# NRF24L01.net
KiCad netlist of a schematic drawn in EAGLE
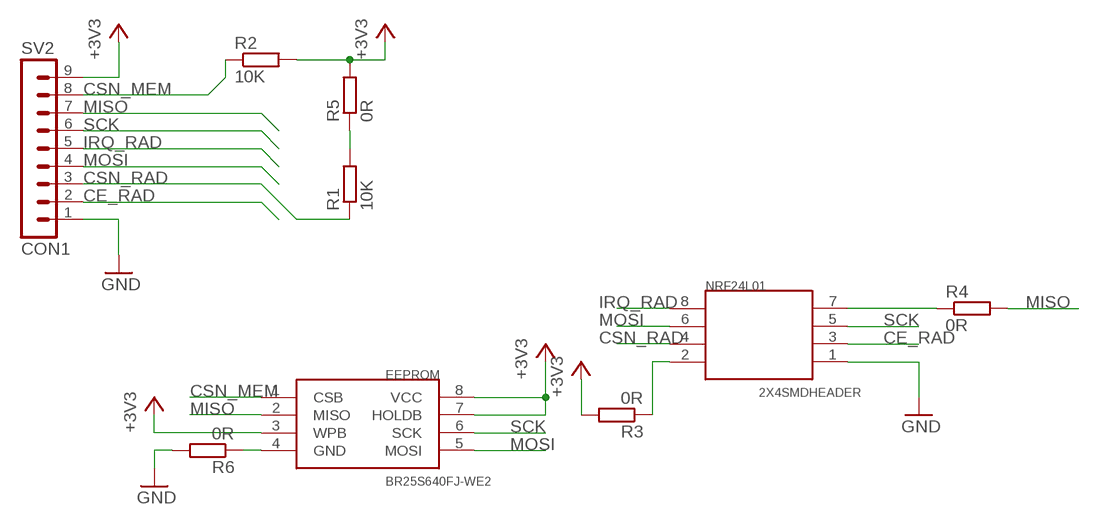
[diagram p0: schematic, sheet 1]

(export (version "E")
  (design (tool "Eeschema 10.0.6"))
  (components
    (comp (ref "EEPROM")
      (value "BR25S640FJ-WE2")
      (footprint "eagle-import:SO8")
      (libsource (lib "eagle-import") (part "BR25S640FJ-WE2"))
    )
    (comp (ref "NRF24L01")
      (value "2X4SMDHEADER")
      (footprint "eagle-import:TSM-110-XX-XXX-DV")
      (libsource (lib "eagle-import") (part "2X4SMDHEADER"))
    )
    (comp (ref "R1")
      (value "10K")
      (footprint "eagle-import:R1206")
      (libsource (lib "eagle-import") (part "R-EU_R1206"))
    )
    (comp (ref "R2")
      (value "10K")
      (footprint "eagle-import:R1206")
      (libsource (lib "eagle-import") (part "R-EU_R1206"))
    )
    (comp (ref "R3")
      (value "0R")
      (footprint "eagle-import:R1206")
      (libsource (lib "eagle-import") (part "R-EU_R1206"))
    )
    (comp (ref "R4")
      (value "0R")
      (footprint "eagle-import:R1206")
      (libsource (lib "eagle-import") (part "R-EU_R1206"))
    )
    (comp (ref "R5")
      (value "0R")
      (footprint "eagle-import:R1206")
      (libsource (lib "eagle-import") (part "R-EU_R1206"))
    )
    (comp (ref "R6")
      (value "0R")
      (footprint "eagle-import:R1206")
      (libsource (lib "eagle-import") (part "R-EU_R1206"))
    )
    (comp (ref "SV2")
      (value "CON1")
      (footprint "eagle-import:MA09-1W")
      (libsource (lib "eagle-import") (part "MA09-1W"))
    )
  )
  (nets
    (net (code "1") (name "+3V3") (class "Default")
      (node (ref "EEPROM") (pin "3") (pinfunction "WPB_3") (pintype "bidirectional"))
      (node (ref "EEPROM") (pin "7") (pinfunction "HOLDB_7") (pintype "bidirectional"))
      (node (ref "EEPROM") (pin "8") (pinfunction "VCC_8") (pintype "bidirectional"))
      (node (ref "R2") (pin "2") (pinfunction "2_2") (pintype "passive"))
      (node (ref "R3") (pin "2") (pinfunction "2_2") (pintype "passive"))
      (node (ref "R5") (pin "2") (pinfunction "2_2") (pintype "passive"))
      (node (ref "SV2") (pin "9") (pinfunction "9_9") (pintype "passive"))
    )
    (net (code "2") (name "/CE_RAD") (class "Default")
      (node (ref "NRF24L01") (pin "3") (pinfunction "3_3") (pintype "bidirectional"))
      (node (ref "SV2") (pin "2") (pinfunction "2_2") (pintype "passive"))
    )
    (net (code "3") (name "/CSN_MEM") (class "Default")
      (node (ref "EEPROM") (pin "1") (pinfunction "CSB_1") (pintype "bidirectional"))
      (node (ref "R2") (pin "1") (pinfunction "1_1") (pintype "passive"))
      (node (ref "SV2") (pin "8") (pinfunction "8_8") (pintype "passive"))
    )
    (net (code "4") (name "/CSN_RAD") (class "Default")
      (node (ref "NRF24L01") (pin "4") (pinfunction "4_4") (pintype "bidirectional"))
      (node (ref "R1") (pin "1") (pinfunction "1_1") (pintype "passive"))
      (node (ref "SV2") (pin "3") (pinfunction "3_3") (pintype "passive"))
    )
    (net (code "5") (name "/IRQ_RAD") (class "Default")
      (node (ref "NRF24L01") (pin "8") (pinfunction "8_8") (pintype "bidirectional"))
      (node (ref "SV2") (pin "5") (pinfunction "5_5") (pintype "passive"))
    )
    (net (code "6") (name "/MISO") (class "Default")
      (node (ref "EEPROM") (pin "2") (pinfunction "MISO_2") (pintype "bidirectional"))
      (node (ref "R4") (pin "2") (pinfunction "2_2") (pintype "passive"))
      (node (ref "SV2") (pin "7") (pinfunction "7_7") (pintype "passive"))
    )
    (net (code "7") (name "/MOSI") (class "Default")
      (node (ref "EEPROM") (pin "5") (pinfunction "MOSI_5") (pintype "bidirectional"))
      (node (ref "NRF24L01") (pin "6") (pinfunction "6_6") (pintype "bidirectional"))
      (node (ref "SV2") (pin "4") (pinfunction "4_4") (pintype "passive"))
    )
    (net (code "8") (name "/SCK") (class "Default")
      (node (ref "EEPROM") (pin "6") (pinfunction "SCK_6") (pintype "bidirectional"))
      (node (ref "NRF24L01") (pin "5") (pinfunction "5_5") (pintype "bidirectional"))
      (node (ref "SV2") (pin "6") (pinfunction "6_6") (pintype "passive"))
    )
    (net (code "9") (name "GND") (class "Default")
      (node (ref "NRF24L01") (pin "1") (pinfunction "1_1") (pintype "bidirectional"))
      (node (ref "R6") (pin "2") (pinfunction "2_2") (pintype "passive"))
      (node (ref "SV2") (pin "1") (pinfunction "1_1") (pintype "passive"))
    )
    (net (code "10") (name "Net-(EEPROM-GND)") (class "Default")
      (node (ref "EEPROM") (pin "4") (pinfunction "GND_4") (pintype "bidirectional"))
      (node (ref "R6") (pin "1") (pinfunction "1_1") (pintype "passive"))
    )
    (net (code "11") (name "Net-(NRF24L01-Pad2)") (class "Default")
      (node (ref "NRF24L01") (pin "2") (pinfunction "2_2") (pintype "bidirectional"))
      (node (ref "R3") (pin "1") (pinfunction "1_1") (pintype "passive"))
    )
    (net (code "12") (name "Net-(NRF24L01-Pad7)") (class "Default")
      (node (ref "NRF24L01") (pin "7") (pinfunction "7_7") (pintype "bidirectional"))
      (node (ref "R4") (pin "1") (pinfunction "1_1") (pintype "passive"))
    )
    (net (code "13") (name "Net-(R1-Pad2)") (class "Default")
      (node (ref "R1") (pin "2") (pinfunction "2_2") (pintype "passive"))
      (node (ref "R5") (pin "1") (pinfunction "1_1") (pintype "passive"))
    )
  )
)
